# 13_Sensors_Onboard.net
KiCad netlist of a schematic drawn in Altium Designer
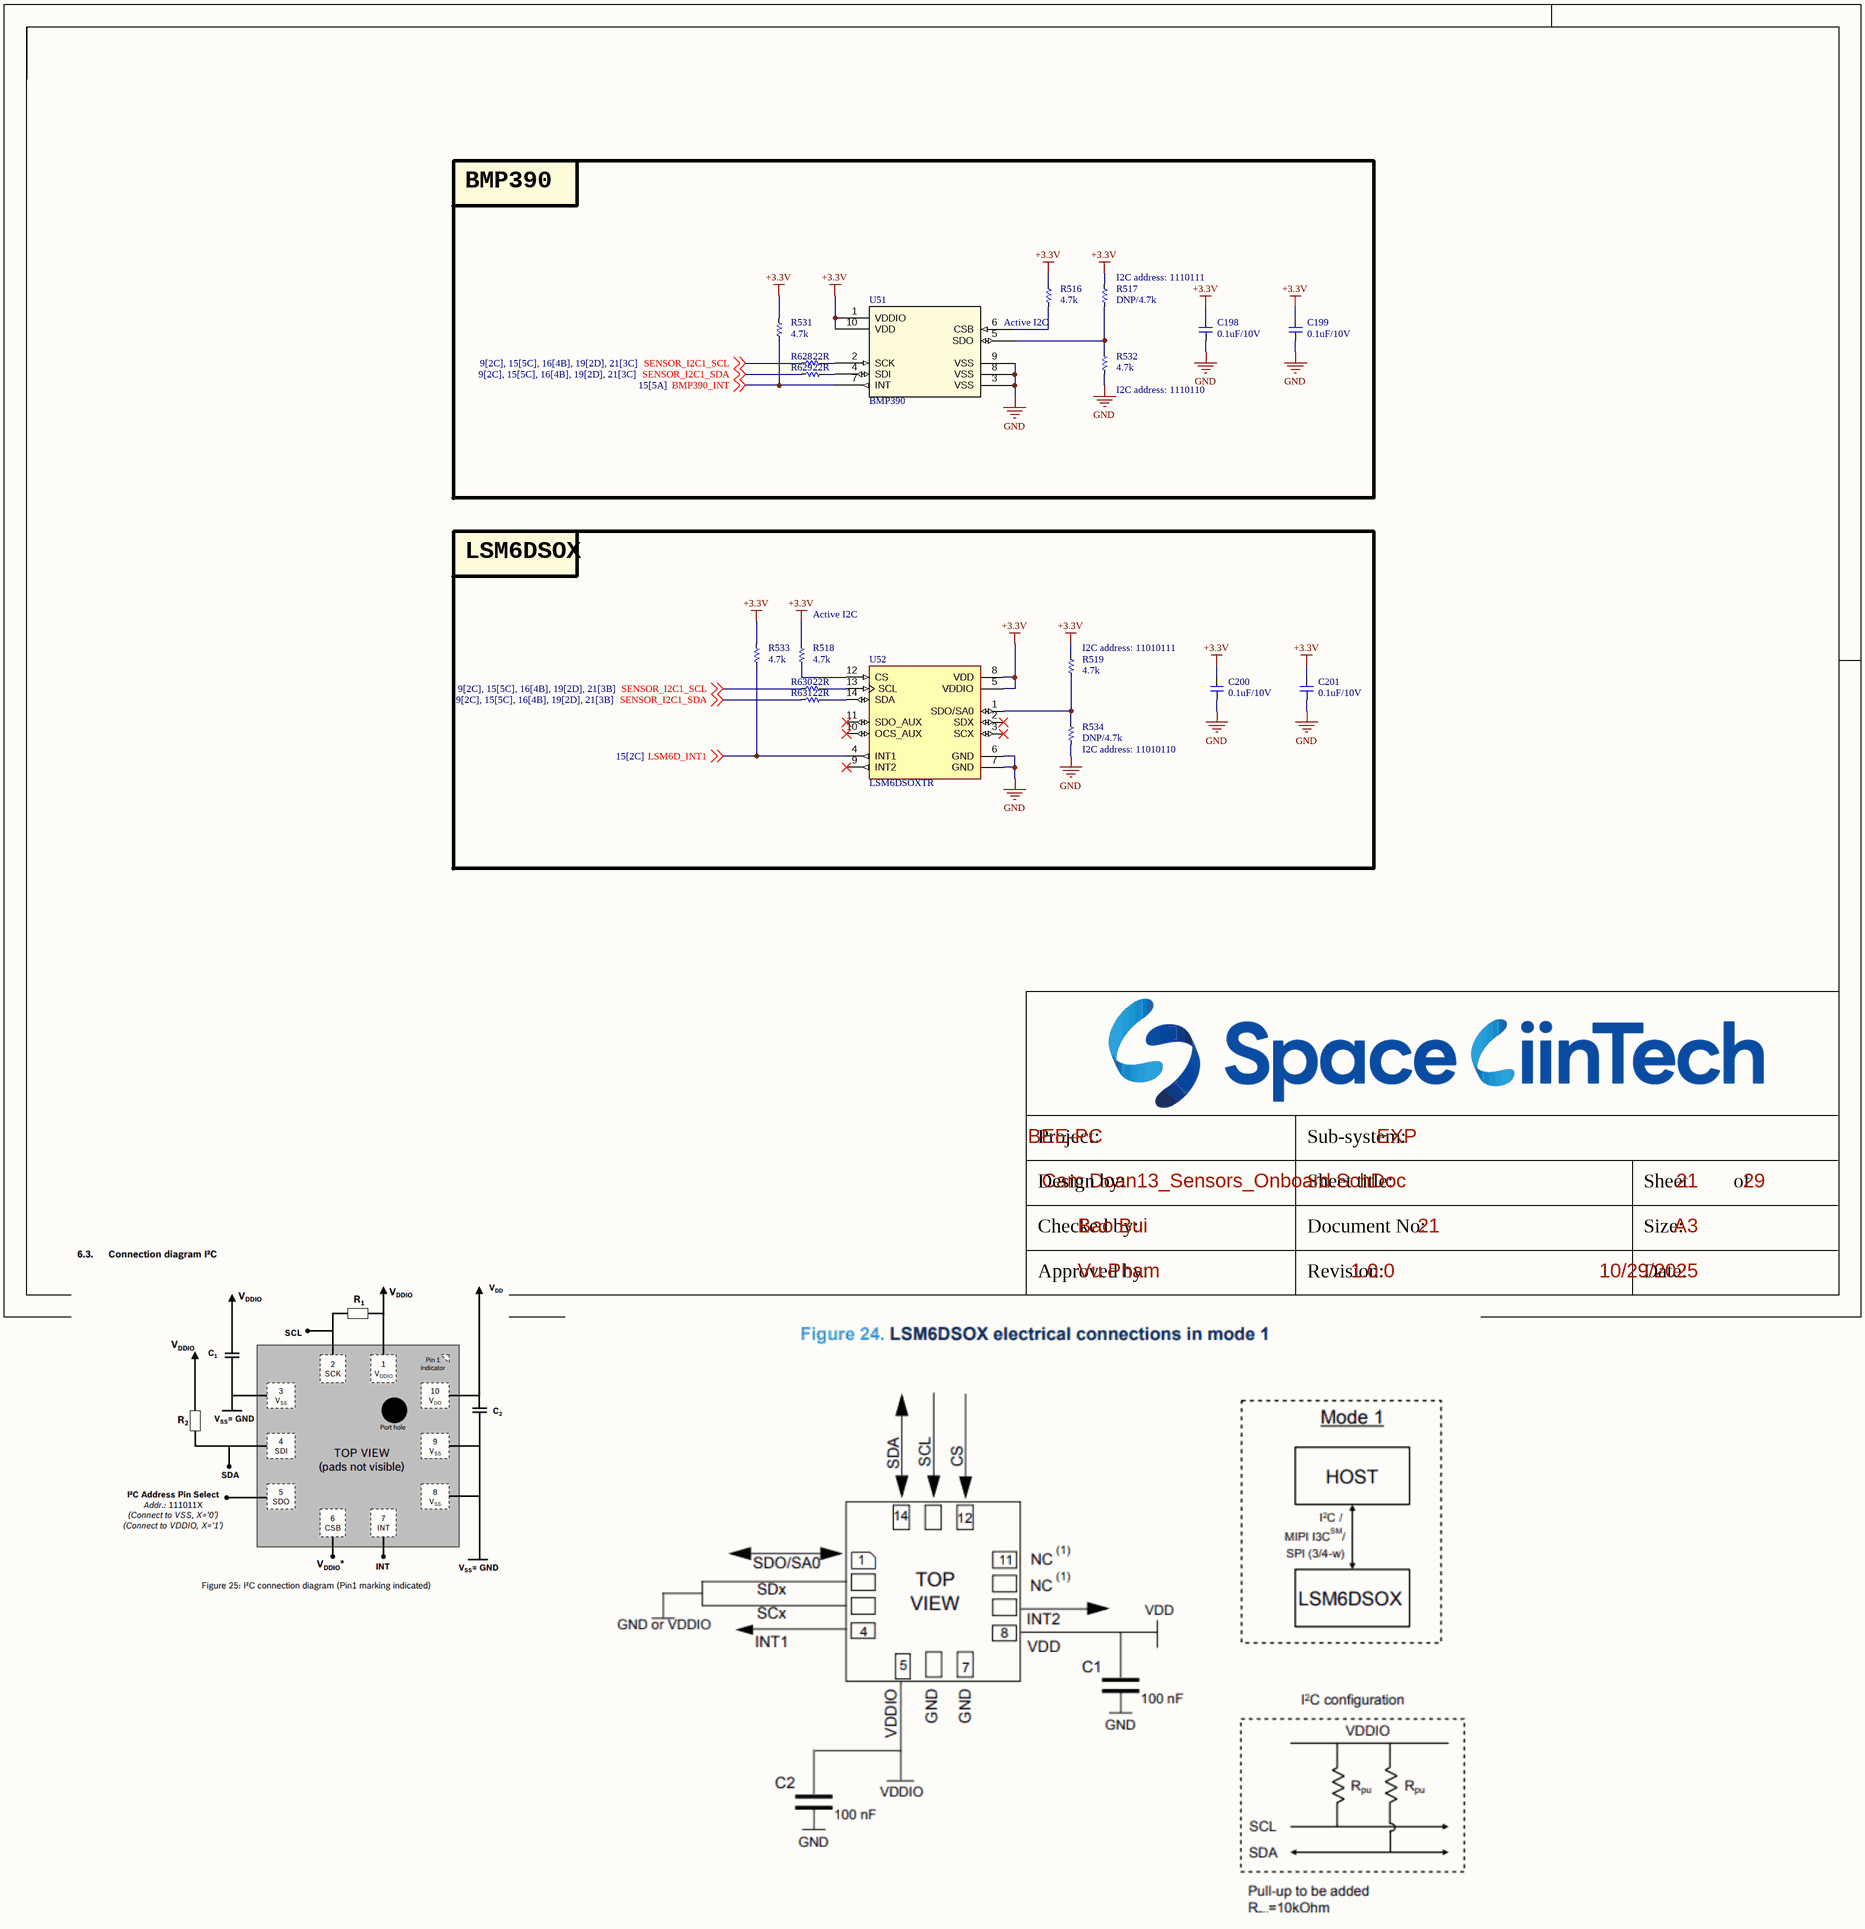
[diagram p0: 13_Sensors_Onboard.SchDoc]

(export (version "E")
  (design (tool "Eeschema 10.0.6"))
  (components
    (comp (ref "C198")
      (value "0.1uF/10V")
      (footprint "CAP_C_1005X60")
      (description "CAP CHIP")
      (libsource (lib "LABLIB") (part "_CAP_C_2"))
    )
    (comp (ref "C199")
      (value "0.1uF/10V")
      (footprint "CAP_C_1005X60")
      (description "CAP CHIP")
      (libsource (lib "LABLIB") (part "_CAP_C_2"))
    )
    (comp (ref "C200")
      (value "0.1uF/10V")
      (footprint "CAP_C_1005X60")
      (description "CAP CHIP")
      (libsource (lib "LABLIB") (part "_CAP_C_2"))
    )
    (comp (ref "C201")
      (value "0.1uF/10V")
      (footprint "CAP_C_1005X60")
      (description "CAP CHIP")
      (libsource (lib "LABLIB") (part "_CAP_C_2"))
    )
    (comp (ref "R516")
      (value "4.7k")
      (footprint "RES_C_1005X40")
      (description "RES")
      (libsource (lib "LABLIB") (part "_RES_B_2"))
    )
    (comp (ref "R517")
      (value "DNP/4.7k")
      (footprint "RES_C_1005X40")
      (description "RES")
      (libsource (lib "LABLIB") (part "_RES_B_2"))
    )
    (comp (ref "R518")
      (value "4.7k")
      (footprint "RES_C_1005X40")
      (description "RES")
      (libsource (lib "LABLIB") (part "_RES_B_2"))
    )
    (comp (ref "R519")
      (value "4.7k")
      (footprint "RES_C_1005X40")
      (description "RES")
      (libsource (lib "LABLIB") (part "_RES_B_2"))
    )
    (comp (ref "R531")
      (value "4.7k")
      (footprint "RES_C_1005X40")
      (description "RES")
      (libsource (lib "LABLIB") (part "_RES_B_2"))
    )
    (comp (ref "R532")
      (value "4.7k")
      (footprint "RES_C_1005X40")
      (description "RES")
      (libsource (lib "LABLIB") (part "_RES_B_2"))
    )
    (comp (ref "R533")
      (value "4.7k")
      (footprint "RES_C_1005X40")
      (description "RES")
      (libsource (lib "LABLIB") (part "_RES_B_2"))
    )
    (comp (ref "R534")
      (value "DNP/4.7k")
      (footprint "RES_C_1005X40")
      (description "RES")
      (libsource (lib "LABLIB") (part "_RES_B_2"))
    )
    (comp (ref "R628")
      (value "22R")
      (footprint "RES_C_1005X40")
      (description "RES")
      (libsource (lib "LABLIB") (part "_RES_B_2"))
    )
    (comp (ref "R629")
      (value "22R")
      (footprint "RES_C_1005X40")
      (description "RES")
      (libsource (lib "LABLIB") (part "_RES_B_2"))
    )
    (comp (ref "R630")
      (value "22R")
      (footprint "RES_C_1005X40")
      (description "RES")
      (libsource (lib "LABLIB") (part "_RES_B_2"))
    )
    (comp (ref "R631")
      (value "22R")
      (footprint "RES_C_1005X40")
      (description "RES")
      (libsource (lib "LABLIB") (part "_RES_B_2"))
    )
    (comp (ref "U51")
      (value "BMP390")
      (footprint "10LGA_2X2X0p75_BOS")
      (description "Description")
      (fields (field (name "COPYRIGHT") "Copyright (C) 2025 Ultra Librarian. All rights reserved."))
      (libsource (lib "LABLIB") (part "BMP390"))
    )
    (comp (ref "U52")
      (value "LSM6DSOXTR")
      (footprint "PQFN50P250X300X86-14N")
      (description "Accelerometer, Gyroscope, 6 Axis Sensor I2C, SPI Output")
      (fields (field (name "MF") "STMicroelectronics"))
      (libsource (lib "LABLIB") (part "LSM6DSOXTR"))
    )
  )
  (nets
    (net (code "1") (name "+3.3V") (class "Default")
      (node (ref "C198") (pin "2") (pinfunction "2_2") (pintype "passive"))
      (node (ref "C199") (pin "2") (pinfunction "2_2") (pintype "passive"))
      (node (ref "C200") (pin "2") (pinfunction "2_2") (pintype "passive"))
      (node (ref "C201") (pin "2") (pinfunction "2_2") (pintype "passive"))
      (node (ref "R516") (pin "1") (pinfunction "1_1") (pintype "passive"))
      (node (ref "R517") (pin "1") (pinfunction "1_1") (pintype "passive"))
      (node (ref "R518") (pin "1") (pinfunction "1_1") (pintype "passive"))
      (node (ref "R519") (pin "1") (pinfunction "1_1") (pintype "passive"))
      (node (ref "R531") (pin "1") (pinfunction "1_1") (pintype "passive"))
      (node (ref "R533") (pin "1") (pinfunction "1_1") (pintype "passive"))
      (node (ref "U51") (pin "1") (pinfunction "VDDIO_1") (pintype "power_in"))
      (node (ref "U51") (pin "10") (pinfunction "VDD_10") (pintype "power_in"))
      (node (ref "U52") (pin "5") (pinfunction "VDDIO_5") (pintype "power_in"))
      (node (ref "U52") (pin "8") (pinfunction "VDD_8") (pintype "power_in"))
    )
    (net (code "2") (name "BMP390_INT") (class "Default")
      (node (ref "R531") (pin "2") (pinfunction "2_2") (pintype "passive"))
      (node (ref "U51") (pin "7") (pinfunction "INT_7") (pintype "output"))
    )
    (net (code "3") (name "GND") (class "Default")
      (node (ref "C198") (pin "1") (pinfunction "1_1") (pintype "passive"))
      (node (ref "C199") (pin "1") (pinfunction "1_1") (pintype "passive"))
      (node (ref "C200") (pin "1") (pinfunction "1_1") (pintype "passive"))
      (node (ref "C201") (pin "1") (pinfunction "1_1") (pintype "passive"))
      (node (ref "R532") (pin "2") (pinfunction "2_2") (pintype "passive"))
      (node (ref "R534") (pin "2") (pinfunction "2_2") (pintype "passive"))
      (node (ref "U51") (pin "3") (pinfunction "VSS_3") (pintype "power_in"))
      (node (ref "U51") (pin "8") (pinfunction "VSS_8") (pintype "power_in"))
      (node (ref "U51") (pin "9") (pinfunction "VSS_9") (pintype "power_in"))
      (node (ref "U52") (pin "6") (pinfunction "GND_6") (pintype "power_in"))
      (node (ref "U52") (pin "7") (pinfunction "GND_7") (pintype "power_in"))
    )
    (net (code "4") (name "LSM6D_INT1") (class "Default")
      (node (ref "R533") (pin "2") (pinfunction "2_2") (pintype "passive"))
      (node (ref "U52") (pin "4") (pinfunction "INT1_4") (pintype "output"))
    )
    (net (code "5") (name "Net-(U51-CSB)") (class "Default")
      (node (ref "R516") (pin "2") (pinfunction "2_2") (pintype "passive"))
      (node (ref "U51") (pin "6") (pinfunction "CSB_6") (pintype "input"))
    )
    (net (code "6") (name "Net-(U51-SCK)") (class "Default")
      (node (ref "R628") (pin "2") (pinfunction "2_2") (pintype "passive"))
      (node (ref "U51") (pin "2") (pinfunction "SCK_2") (pintype "input"))
    )
    (net (code "7") (name "Net-(U51-SDI)") (class "Default")
      (node (ref "R629") (pin "2") (pinfunction "2_2") (pintype "passive"))
      (node (ref "U51") (pin "4") (pinfunction "SDI_4") (pintype "bidirectional"))
    )
    (net (code "8") (name "Net-(U51-SDO)") (class "Default")
      (node (ref "R517") (pin "2") (pinfunction "2_2") (pintype "passive"))
      (node (ref "R532") (pin "1") (pinfunction "1_1") (pintype "passive"))
      (node (ref "U51") (pin "5") (pinfunction "SDO_5") (pintype "bidirectional"))
    )
    (net (code "9") (name "Net-(U52-CS)") (class "Default")
      (node (ref "R518") (pin "2") (pinfunction "2_2") (pintype "passive"))
      (node (ref "U52") (pin "12") (pinfunction "CS_12") (pintype "input"))
    )
    (net (code "10") (name "Net-(U52-SCL)") (class "Default")
      (node (ref "R630") (pin "2") (pinfunction "2_2") (pintype "passive"))
      (node (ref "U52") (pin "13") (pinfunction "SCL_13") (pintype "input"))
    )
    (net (code "11") (name "Net-(U52-SDA)") (class "Default")
      (node (ref "R631") (pin "2") (pinfunction "2_2") (pintype "passive"))
      (node (ref "U52") (pin "14") (pinfunction "SDA_14") (pintype "bidirectional"))
    )
    (net (code "12") (name "Net-(U52-SDO{slash}SA0)") (class "Default")
      (node (ref "R519") (pin "2") (pinfunction "2_2") (pintype "passive"))
      (node (ref "R534") (pin "1") (pinfunction "1_1") (pintype "passive"))
      (node (ref "U52") (pin "1") (pinfunction "SDO/SA0_1") (pintype "bidirectional"))
    )
    (net (code "13") (name "SENSOR_I2C1_SCL") (class "Default")
      (node (ref "R628") (pin "1") (pinfunction "1_1") (pintype "passive"))
      (node (ref "R630") (pin "1") (pinfunction "1_1") (pintype "passive"))
    )
    (net (code "14") (name "SENSOR_I2C1_SDA") (class "Default")
      (node (ref "R629") (pin "1") (pinfunction "1_1") (pintype "passive"))
      (node (ref "R631") (pin "1") (pinfunction "1_1") (pintype "passive"))
    )
    (net (code "15") (name "unconnected-(U52-INT2-Pad9)") (class "Default")
      (node (ref "U52") (pin "9") (pinfunction "INT2_9") (pintype "output+no_connect"))
    )
    (net (code "16") (name "unconnected-(U52-OCS_AUX-Pad10)") (class "Default")
      (node (ref "U52") (pin "10") (pinfunction "OCS_AUX_10") (pintype "bidirectional+no_connect"))
    )
    (net (code "17") (name "unconnected-(U52-SCX-Pad3)") (class "Default")
      (node (ref "U52") (pin "3") (pinfunction "SCX_3") (pintype "bidirectional+no_connect"))
    )
    (net (code "18") (name "unconnected-(U52-SDO_AUX-Pad11)") (class "Default")
      (node (ref "U52") (pin "11") (pinfunction "SDO_AUX_11") (pintype "bidirectional+no_connect"))
    )
    (net (code "19") (name "unconnected-(U52-SDX-Pad2)") (class "Default")
      (node (ref "U52") (pin "2") (pinfunction "SDX_2") (pintype "bidirectional+no_connect"))
    )
  )
)
